# pfetreg.net
KiCad netlist of a schematic drawn in EAGLE
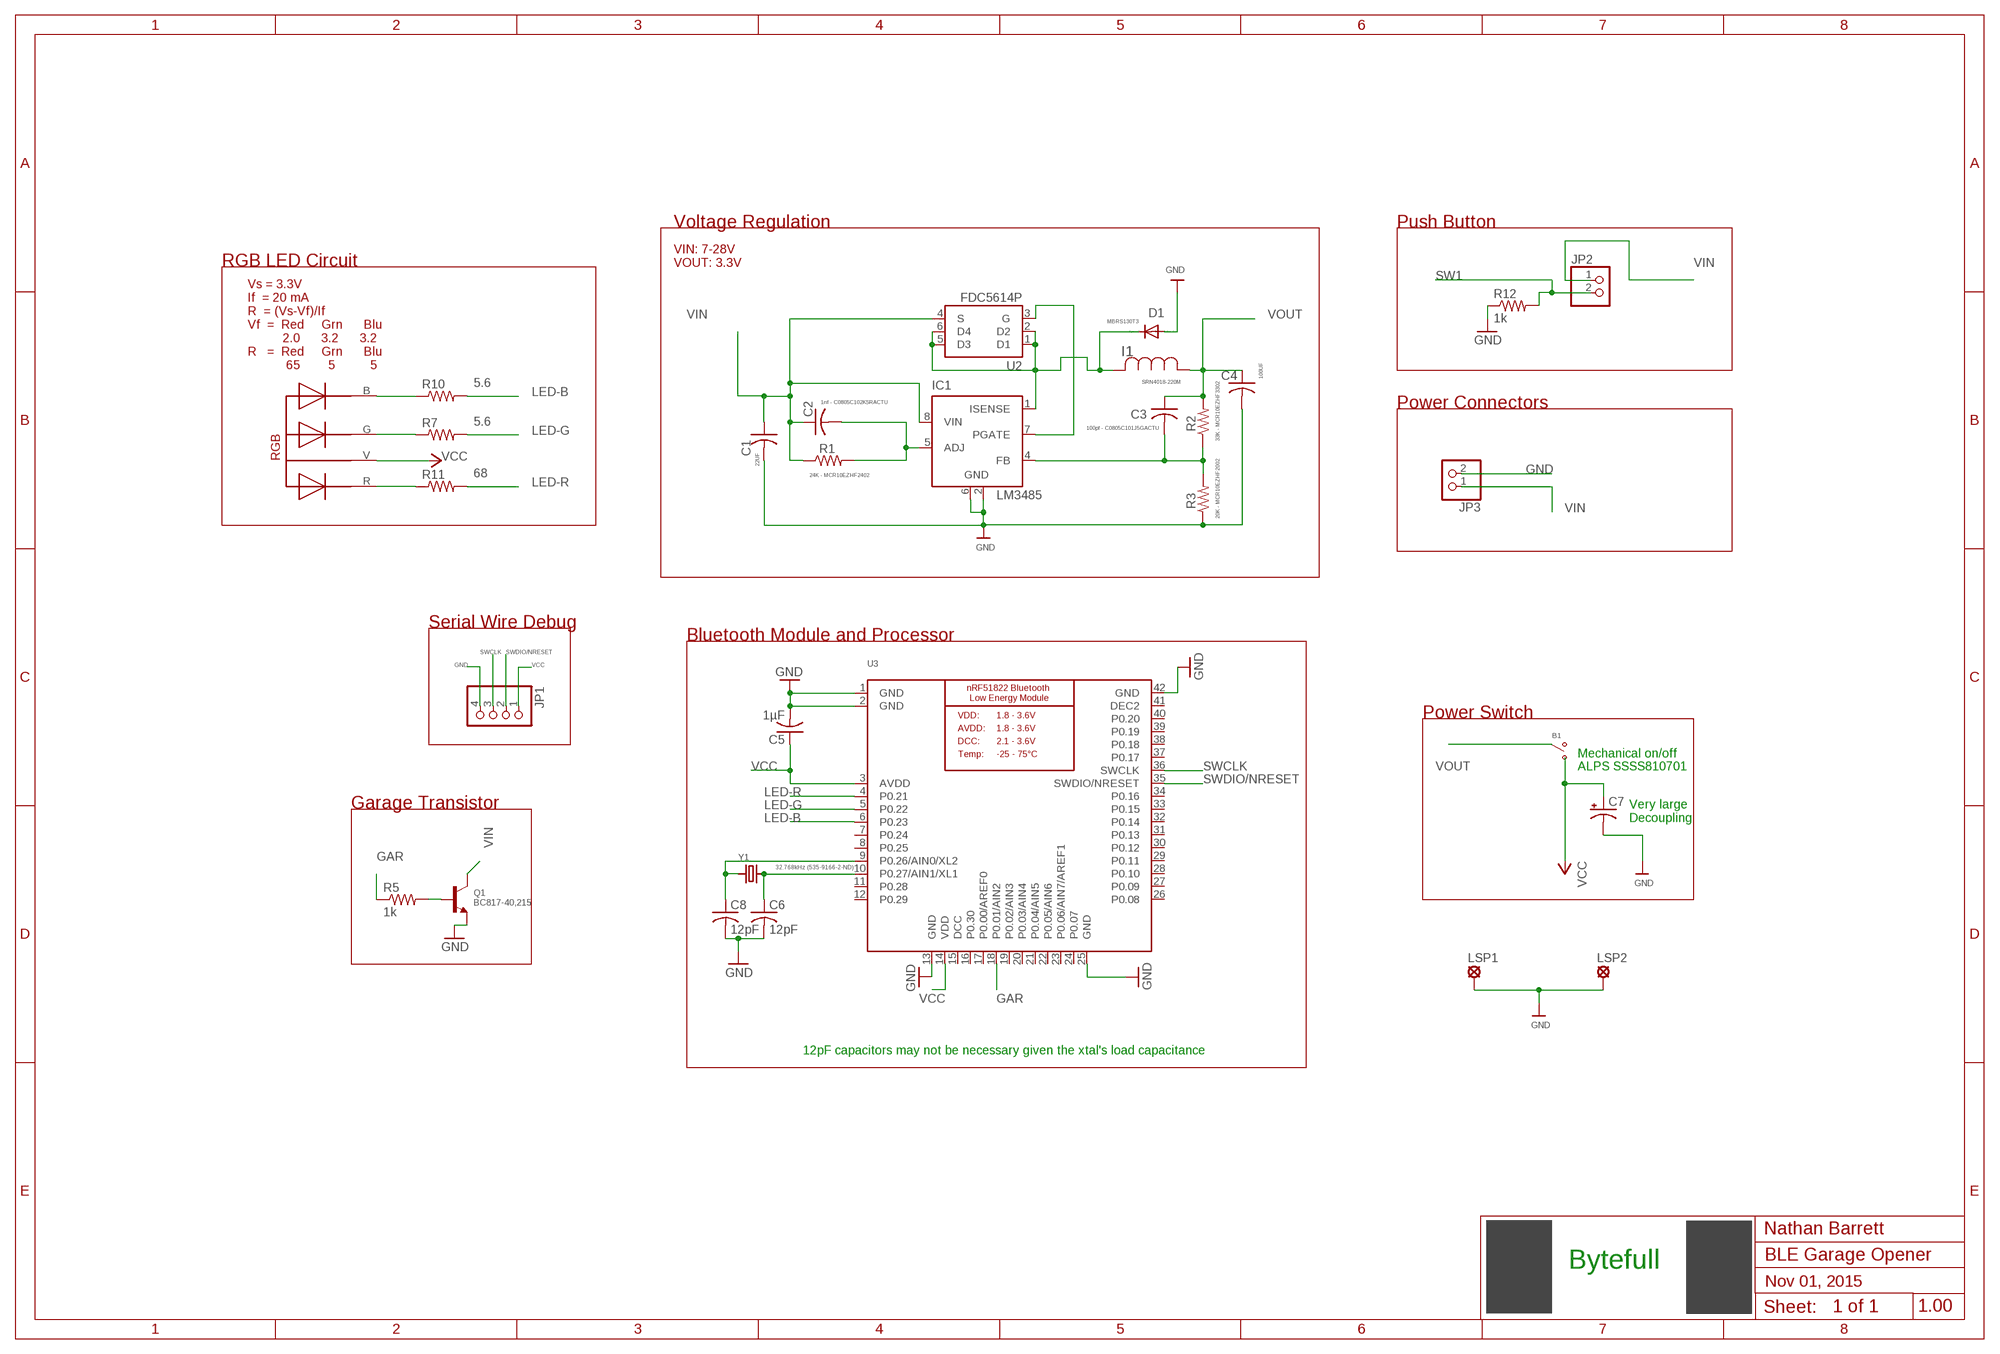
[diagram p0: schematic, sheet 1]

(export (version "E")
  (design (tool "Eeschema 10.0.6"))
  (components
    (comp (ref "B1")
      (value "SSSS810701")
      (footprint "eagle-import:SSSS810701")
      (libsource (lib "eagle-import") (part "SSSS810701"))
    )
    (comp (ref "C1")
      (value "22UF")
      (footprint "eagle-import:CAPCP7343X430N")
      (fields (field (name "MPN") "F931V226MNC"))
      (libsource (lib "eagle-import") (part "F931V226MNC"))
    )
    (comp (ref "C2")
      (value "1nf - C0805C102K5RACTU")
      (footprint "eagle-import:C0805K")
      (libsource (lib "eagle-import") (part "C-USC0805K"))
    )
    (comp (ref "C3")
      (value "100pf - C0805C101J5GACTU")
      (footprint "eagle-import:C0805K")
      (libsource (lib "eagle-import") (part "C-USC0805K"))
    )
    (comp (ref "C4")
      (value "100UF")
      (footprint "eagle-import:CAPCP7343X430N")
      (fields (field (name "MPN") "6TPC100M"))
      (libsource (lib "eagle-import") (part "6TPC100M"))
    )
    (comp (ref "C5")
      (value "1µF")
      (footprint "eagle-import:C0805K")
      (libsource (lib "eagle-import") (part "HelloWorld_C-USC0805K"))
    )
    (comp (ref "C6")
      (value "12pF")
      (footprint "eagle-import:C0805")
      (libsource (lib "eagle-import") (part "HelloWorld_C-USC0805"))
    )
    (comp (ref "C7")
      (value "CPOL-USE5-10.5")
      (footprint "eagle-import:E5-10,5")
      (libsource (lib "eagle-import") (part "CPOL-USE5-10.5"))
    )
    (comp (ref "C8")
      (value "12pF")
      (footprint "eagle-import:C0805")
      (libsource (lib "eagle-import") (part "HelloWorld_C-USC0805"))
    )
    (comp (ref "D1")
      (value "MBRS130T3")
      (footprint "eagle-import:DO214AA")
      (libsource (lib "eagle-import") (part "DIODE-DO214AA"))
    )
    (comp (ref "I1")
      (value "SRN4018-220M")
      (footprint "eagle-import:SRN4018-220M")
      (libsource (lib "eagle-import") (part "SRN4018-220M"))
    )
    (comp (ref "IC1")
      (value "LM3485")
      (footprint "eagle-import:MSOP08")
      (libsource (lib "eagle-import") (part "LM3485"))
    )
    (comp (ref "JP1")
      (value "PINHD-1X4")
      (footprint "eagle-import:1X04")
      (libsource (lib "eagle-import") (part "PINHD-1X4"))
    )
    (comp (ref "JP2")
      (value "PINHD-1X2")
      (footprint "eagle-import:1X02")
      (libsource (lib "eagle-import") (part "PINHD-1X2"))
    )
    (comp (ref "JP3")
      (value "PINHD-1X2")
      (footprint "eagle-import:1X02")
      (libsource (lib "eagle-import") (part "PINHD-1X2"))
    )
    (comp (ref "LSP1")
      (value "LSP11")
      (footprint "eagle-import:LSP11")
      (libsource (lib "eagle-import") (part "LSP11"))
    )
    (comp (ref "LSP2")
      (value "LSP11")
      (footprint "eagle-import:LSP11")
      (libsource (lib "eagle-import") (part "LSP11"))
    )
    (comp (ref "Q1")
      (value "BC817-40,215")
      (footprint "eagle-import:SOT23-R")
      (libsource (lib "eagle-import") (part "TRANSISTOR_NPN"))
    )
    (comp (ref "R1")
      (value "24K - MCR10EZHF2402")
      (footprint "eagle-import:R0805W")
      (libsource (lib "eagle-import") (part "R-US_R0805W"))
    )
    (comp (ref "R2")
      (value "33K - MCR10EZHF3302")
      (footprint "eagle-import:R0805W")
      (libsource (lib "eagle-import") (part "R-US_R0805W"))
    )
    (comp (ref "R3")
      (value "20K - MCR10EZHF2002")
      (footprint "eagle-import:R0805W")
      (libsource (lib "eagle-import") (part "R-US_R0805W"))
    )
    (comp (ref "R5")
      (value "1k")
      (footprint "eagle-import:R0805")
      (libsource (lib "eagle-import") (part "HelloWorld_R-US_R0805"))
    )
    (comp (ref "R7")
      (value "5.6")
      (footprint "eagle-import:R0805")
      (libsource (lib "eagle-import") (part "HelloWorld_R-US_R0805"))
    )
    (comp (ref "R10")
      (value "5.6")
      (footprint "eagle-import:R0805")
      (libsource (lib "eagle-import") (part "HelloWorld_R-US_R0805"))
    )
    (comp (ref "R11")
      (value "68")
      (footprint "eagle-import:R0805")
      (libsource (lib "eagle-import") (part "HelloWorld_R-US_R0805"))
    )
    (comp (ref "R12")
      (value "1k")
      (footprint "eagle-import:R0805")
      (libsource (lib "eagle-import") (part "HelloWorld_R-US_R0805"))
    )
    (comp (ref "RGB")
      (value "5MMRGBLED")
      (footprint "eagle-import:LED5MMRGB")
      (libsource (lib "eagle-import") (part "5MMRGBLED"))
    )
    (comp (ref "U2")
      (value "FDC5614PSOT-23")
      (footprint "eagle-import:SOT23-6")
      (libsource (lib "eagle-import") (part "FDC5614PSOT-23"))
    )
    (comp (ref "U3")
      (value "NRF51822_MODULE_MDBT40")
      (footprint "eagle-import:BLE_MODULE_RAYTAC_MDBT40")
      (libsource (lib "eagle-import") (part "NRF51822_MODULE_MDBT40"))
    )
    (comp (ref "Y1")
      (value "CRYSTAL8X3.8SMT")
      (footprint "eagle-import:CRYSTAL_8X3.8")
      (libsource (lib "eagle-import") (part "CRYSTAL8X3.8SMT"))
    )
  )
  (nets
    (net (code "1") (name "/DCC") (class "Default")
      (node (ref "U3") (pin "15") (pinfunction "DCC_15") (pintype "power_in"))
    )
    (net (code "2") (name "/DEC2") (class "Default")
      (node (ref "U3") (pin "41") (pinfunction "DEC2_41") (pintype "power_in"))
    )
    (net (code "3") (name "/GAR") (class "Default")
      (node (ref "R5") (pin "1") (pinfunction "1_1") (pintype "passive"))
      (node (ref "U3") (pin "18") (pinfunction "P0.01/AIN2_18") (pintype "bidirectional"))
    )
    (net (code "4") (name "/LED-B") (class "Default")
      (node (ref "R10") (pin "2") (pinfunction "2_2") (pintype "passive"))
      (node (ref "U3") (pin "6") (pinfunction "P0.23_6") (pintype "bidirectional"))
    )
    (net (code "5") (name "/LED-G") (class "Default")
      (node (ref "R7") (pin "2") (pinfunction "2_2") (pintype "passive"))
      (node (ref "U3") (pin "5") (pinfunction "P0.22_5") (pintype "bidirectional"))
    )
    (net (code "6") (name "/LED-R") (class "Default")
      (node (ref "R11") (pin "2") (pinfunction "2_2") (pintype "passive"))
      (node (ref "U3") (pin "4") (pinfunction "P0.21_4") (pintype "bidirectional"))
    )
    (net (code "7") (name "/SW1") (class "Default")
      (node (ref "JP2") (pin "2") (pinfunction "2_2") (pintype "passive"))
      (node (ref "R12") (pin "2") (pinfunction "2_2") (pintype "passive"))
    )
    (net (code "8") (name "/SWCLK") (class "Default")
      (node (ref "JP1") (pin "3") (pinfunction "3_3") (pintype "passive"))
      (node (ref "U3") (pin "36") (pinfunction "SWCLK_36") (pintype "bidirectional"))
    )
    (net (code "9") (name "/SWDIO{slash}NRESET") (class "Default")
      (node (ref "JP1") (pin "2") (pinfunction "2_2") (pintype "passive"))
      (node (ref "U3") (pin "35") (pinfunction "SWDIO/NRESET_35") (pintype "bidirectional"))
    )
    (net (code "10") (name "/VIN") (class "Default")
      (node (ref "C1") (pin "1") (pinfunction "I1_1") (pintype "passive"))
      (node (ref "C2") (pin "1") (pinfunction "1_1") (pintype "passive"))
      (node (ref "IC1") (pin "8") (pinfunction "VIN_8") (pintype "input"))
      (node (ref "JP2") (pin "1") (pinfunction "1_1") (pintype "passive"))
      (node (ref "JP3") (pin "1") (pinfunction "1_1") (pintype "passive"))
      (node (ref "Q1") (pin "3") (pinfunction "C_3") (pintype "passive"))
      (node (ref "R1") (pin "1") (pinfunction "1_1") (pintype "passive"))
      (node (ref "U2") (pin "4") (pinfunction "S_4") (pintype "bidirectional"))
    )
    (net (code "11") (name "/VOUT") (class "Default")
      (node (ref "B1") (pin "2") (pinfunction "COM_2") (pintype "bidirectional"))
      (node (ref "C3") (pin "1") (pinfunction "1_1") (pintype "passive"))
      (node (ref "C4") (pin "1") (pinfunction "I1_1") (pintype "passive"))
      (node (ref "I1") (pin "2") (pinfunction "I2_2") (pintype "passive"))
      (node (ref "R2") (pin "2") (pinfunction "2_2") (pintype "passive"))
    )
    (net (code "12") (name "GND") (class "Default")
      (node (ref "C1") (pin "2") (pinfunction "I2_2") (pintype "passive"))
      (node (ref "C4") (pin "2") (pinfunction "I2_2") (pintype "passive"))
      (node (ref "C5") (pin "2") (pinfunction "2_2") (pintype "passive"))
      (node (ref "C6") (pin "2") (pinfunction "2_2") (pintype "passive"))
      (node (ref "C7") (pin "-") (pinfunction "-_-") (pintype "passive"))
      (node (ref "C8") (pin "2") (pinfunction "2_2") (pintype "passive"))
      (node (ref "D1") (pin "A") (pinfunction "A_A") (pintype "passive"))
      (node (ref "IC1") (pin "2") (pinfunction "GND_2") (pintype "power_in"))
      (node (ref "IC1") (pin "6") (pinfunction "GND_6") (pintype "power_in"))
      (node (ref "JP1") (pin "4") (pinfunction "4_4") (pintype "passive"))
      (node (ref "JP3") (pin "2") (pinfunction "2_2") (pintype "passive"))
      (node (ref "LSP1") (pin "MP") (pinfunction "MP_MP") (pintype "passive"))
      (node (ref "LSP2") (pin "MP") (pinfunction "MP_MP") (pintype "passive"))
      (node (ref "Q1") (pin "2") (pinfunction "E_2") (pintype "passive"))
      (node (ref "R12") (pin "1") (pinfunction "1_1") (pintype "passive"))
      (node (ref "R3") (pin "1") (pinfunction "1_1") (pintype "passive"))
      (node (ref "U3") (pin "1") (pinfunction "GND_1") (pintype "power_in"))
      (node (ref "U3") (pin "13") (pinfunction "GND_13") (pintype "power_in"))
      (node (ref "U3") (pin "2") (pinfunction "GND_2") (pintype "power_in"))
      (node (ref "U3") (pin "25") (pinfunction "GND_25") (pintype "power_in"))
      (node (ref "U3") (pin "42") (pinfunction "GND_42") (pintype "power_in"))
    )
    (net (code "13") (name "Net-(I1-I1)") (class "Default")
      (node (ref "D1") (pin "C") (pinfunction "C_C") (pintype "passive"))
      (node (ref "I1") (pin "1") (pinfunction "I1_1") (pintype "passive"))
      (node (ref "IC1") (pin "1") (pinfunction "ISENSE_1") (pintype "input"))
      (node (ref "U2") (pin "1") (pinfunction "D1_1") (pintype "bidirectional"))
      (node (ref "U2") (pin "2") (pinfunction "D2_2") (pintype "bidirectional"))
      (node (ref "U2") (pin "5") (pinfunction "D3_5") (pintype "bidirectional"))
      (node (ref "U2") (pin "6") (pinfunction "D4_6") (pintype "bidirectional"))
    )
    (net (code "14") (name "Net-(IC1-ADJ)") (class "Default")
      (node (ref "C2") (pin "2") (pinfunction "2_2") (pintype "passive"))
      (node (ref "IC1") (pin "5") (pinfunction "ADJ_5") (pintype "input"))
      (node (ref "R1") (pin "2") (pinfunction "2_2") (pintype "passive"))
    )
    (net (code "15") (name "Net-(IC1-FB)") (class "Default")
      (node (ref "C3") (pin "2") (pinfunction "2_2") (pintype "passive"))
      (node (ref "IC1") (pin "4") (pinfunction "FB_4") (pintype "input"))
      (node (ref "R2") (pin "1") (pinfunction "1_1") (pintype "passive"))
      (node (ref "R3") (pin "2") (pinfunction "2_2") (pintype "passive"))
    )
    (net (code "16") (name "Net-(IC1-PGATE)") (class "Default")
      (node (ref "IC1") (pin "7") (pinfunction "PGATE_7") (pintype "output"))
      (node (ref "U2") (pin "3") (pinfunction "G_3") (pintype "bidirectional"))
    )
    (net (code "17") (name "Net-(Q1-B)") (class "Default")
      (node (ref "Q1") (pin "1") (pinfunction "B_1") (pintype "passive"))
      (node (ref "R5") (pin "2") (pinfunction "2_2") (pintype "passive"))
    )
    (net (code "18") (name "Net-(R7-Pad1)") (class "Default")
      (node (ref "R7") (pin "1") (pinfunction "1_1") (pintype "passive"))
      (node (ref "RGB") (pin "G") (pinfunction "G_G") (pintype "bidirectional"))
    )
    (net (code "19") (name "Net-(R10-Pad1)") (class "Default")
      (node (ref "R10") (pin "1") (pinfunction "1_1") (pintype "passive"))
      (node (ref "RGB") (pin "B") (pinfunction "B_B") (pintype "bidirectional"))
    )
    (net (code "20") (name "Net-(R11-Pad1)") (class "Default")
      (node (ref "R11") (pin "1") (pinfunction "1_1") (pintype "passive"))
      (node (ref "RGB") (pin "R") (pinfunction "R_R") (pintype "bidirectional"))
    )
    (net (code "21") (name "Net-(U3-P0.26{slash}AIN0{slash}XL2)") (class "Default")
      (node (ref "C8") (pin "1") (pinfunction "1_1") (pintype "passive"))
      (node (ref "U3") (pin "9") (pinfunction "P0.26/AIN0/XL2_9") (pintype "bidirectional"))
      (node (ref "Y1") (pin "P$1") (pinfunction "1_P$1") (pintype "passive"))
    )
    (net (code "22") (name "Net-(U3-P0.27{slash}AIN1{slash}XL1)") (class "Default")
      (node (ref "C6") (pin "1") (pinfunction "1_1") (pintype "passive"))
      (node (ref "U3") (pin "10") (pinfunction "P0.27/AIN1/XL1_10") (pintype "bidirectional"))
      (node (ref "Y1") (pin "P$4") (pinfunction "2_P$4") (pintype "passive"))
    )
    (net (code "23") (name "VCC") (class "Default")
      (node (ref "B1") (pin "1") (pinfunction "B_1") (pintype "bidirectional"))
      (node (ref "C5") (pin "1") (pinfunction "1_1") (pintype "passive"))
      (node (ref "C7") (pin "+") (pinfunction "+_+") (pintype "passive"))
      (node (ref "JP1") (pin "1") (pinfunction "1_1") (pintype "passive"))
      (node (ref "RGB") (pin "V") (pinfunction "V_V") (pintype "bidirectional"))
      (node (ref "U3") (pin "14") (pinfunction "VDD_14") (pintype "power_in"))
      (node (ref "U3") (pin "3") (pinfunction "AVDD_3") (pintype "power_in"))
    )
    (net (code "24") (name "unconnected-(B1-A-Pad3)") (class "Default")
      (node (ref "B1") (pin "3") (pinfunction "A_3") (pintype "bidirectional"))
    )
    (net (code "25") (name "unconnected-(U3-P0.00{slash}AREF0-Pad17)") (class "Default")
      (node (ref "U3") (pin "17") (pinfunction "P0.00/AREF0_17") (pintype "bidirectional"))
    )
    (net (code "26") (name "unconnected-(U3-P0.02{slash}AIN3-Pad19)") (class "Default")
      (node (ref "U3") (pin "19") (pinfunction "P0.02/AIN3_19") (pintype "bidirectional"))
    )
    (net (code "27") (name "unconnected-(U3-P0.03{slash}AIN4-Pad20)") (class "Default")
      (node (ref "U3") (pin "20") (pinfunction "P0.03/AIN4_20") (pintype "bidirectional"))
    )
    (net (code "28") (name "unconnected-(U3-P0.04{slash}AIN5-Pad21)") (class "Default")
      (node (ref "U3") (pin "21") (pinfunction "P0.04/AIN5_21") (pintype "bidirectional"))
    )
    (net (code "29") (name "unconnected-(U3-P0.05{slash}AIN6-Pad22)") (class "Default")
      (node (ref "U3") (pin "22") (pinfunction "P0.05/AIN6_22") (pintype "bidirectional"))
    )
    (net (code "30") (name "unconnected-(U3-P0.06{slash}AIN7{slash}AREF1-Pad23)") (class "Default")
      (node (ref "U3") (pin "23") (pinfunction "P0.06/AIN7/AREF1_23") (pintype "bidirectional"))
    )
    (net (code "31") (name "unconnected-(U3-P0.07-Pad24)") (class "Default")
      (node (ref "U3") (pin "24") (pinfunction "P0.07_24") (pintype "bidirectional"))
    )
    (net (code "32") (name "unconnected-(U3-P0.08-Pad26)") (class "Default")
      (node (ref "U3") (pin "26") (pinfunction "P0.08_26") (pintype "bidirectional"))
    )
    (net (code "33") (name "unconnected-(U3-P0.09-Pad27)") (class "Default")
      (node (ref "U3") (pin "27") (pinfunction "P0.09_27") (pintype "bidirectional"))
    )
    (net (code "34") (name "unconnected-(U3-P0.10-Pad28)") (class "Default")
      (node (ref "U3") (pin "28") (pinfunction "P0.10_28") (pintype "bidirectional"))
    )
    (net (code "35") (name "unconnected-(U3-P0.11-Pad29)") (class "Default")
      (node (ref "U3") (pin "29") (pinfunction "P0.11_29") (pintype "bidirectional"))
    )
    (net (code "36") (name "unconnected-(U3-P0.12-Pad30)") (class "Default")
      (node (ref "U3") (pin "30") (pinfunction "P0.12_30") (pintype "bidirectional"))
    )
    (net (code "37") (name "unconnected-(U3-P0.13-Pad31)") (class "Default")
      (node (ref "U3") (pin "31") (pinfunction "P0.13_31") (pintype "bidirectional"))
    )
    (net (code "38") (name "unconnected-(U3-P0.14-Pad32)") (class "Default")
      (node (ref "U3") (pin "32") (pinfunction "P0.14_32") (pintype "bidirectional"))
    )
    (net (code "39") (name "unconnected-(U3-P0.15-Pad33)") (class "Default")
      (node (ref "U3") (pin "33") (pinfunction "P0.15_33") (pintype "bidirectional"))
    )
    (net (code "40") (name "unconnected-(U3-P0.16-Pad34)") (class "Default")
      (node (ref "U3") (pin "34") (pinfunction "P0.16_34") (pintype "bidirectional"))
    )
    (net (code "41") (name "unconnected-(U3-P0.17-Pad37)") (class "Default")
      (node (ref "U3") (pin "37") (pinfunction "P0.17_37") (pintype "bidirectional"))
    )
    (net (code "42") (name "unconnected-(U3-P0.18-Pad38)") (class "Default")
      (node (ref "U3") (pin "38") (pinfunction "P0.18_38") (pintype "bidirectional"))
    )
    (net (code "43") (name "unconnected-(U3-P0.19-Pad39)") (class "Default")
      (node (ref "U3") (pin "39") (pinfunction "P0.19_39") (pintype "bidirectional"))
    )
    (net (code "44") (name "unconnected-(U3-P0.20-Pad40)") (class "Default")
      (node (ref "U3") (pin "40") (pinfunction "P0.20_40") (pintype "bidirectional"))
    )
    (net (code "45") (name "unconnected-(U3-P0.24-Pad7)") (class "Default")
      (node (ref "U3") (pin "7") (pinfunction "P0.24_7") (pintype "bidirectional"))
    )
    (net (code "46") (name "unconnected-(U3-P0.25-Pad8)") (class "Default")
      (node (ref "U3") (pin "8") (pinfunction "P0.25_8") (pintype "bidirectional"))
    )
    (net (code "47") (name "unconnected-(U3-P0.28-Pad11)") (class "Default")
      (node (ref "U3") (pin "11") (pinfunction "P0.28_11") (pintype "bidirectional"))
    )
    (net (code "48") (name "unconnected-(U3-P0.29-Pad12)") (class "Default")
      (node (ref "U3") (pin "12") (pinfunction "P0.29_12") (pintype "bidirectional"))
    )
    (net (code "49") (name "unconnected-(U3-P0.30-Pad16)") (class "Default")
      (node (ref "U3") (pin "16") (pinfunction "P0.30_16") (pintype "bidirectional"))
    )
  )
)
